# Motor_Controllers.net
KiCad netlist of a schematic drawn in Altium Designer
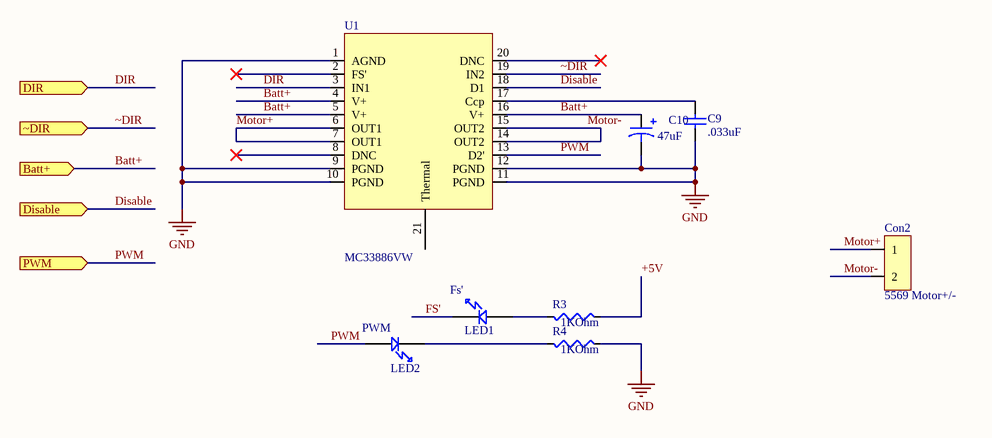
[diagram p0: Motor Controllers.SchDoc]

(export (version "E")
  (design (tool "Eeschema 10.0.6"))
  (components
    (comp (ref "C9")
      (value ".033uF")
      (footprint "PassiveComponents:0805 (2012) Capacitor")
      (description "Capacitor")
      (libsource (lib "PassiveComponents") (part "Capacitor (non-polarized)"))
    )
    (comp (ref "C10")
      (value "47uF")
      (footprint "PassiveComponents:Radial_6.3mmDia_SM_D")
      (description "Capacitor (polarized)")
      (libsource (lib "PassiveComponents") (part "Capacitor (polarized)"))
    )
    (comp (ref "Con2")
      (value "5569 Motor+/-")
      (footprint "Molex:5569 Mini-Fit Jr 2-Pos Right Angle w/ PCB Mounting Flange")
      (libsource (lib "Molex") (part "5569 Mini-Fit Jr 2-Pos Right Angle"))
    )
    (comp (ref "LED1")
      (value "Fs'")
      (footprint "LEDs:LED 0805")
      (description "Standard LED")
      (libsource (lib "PassiveComponents") (part "LED"))
    )
    (comp (ref "LED2")
      (value "PWM")
      (footprint "LEDs:LED 0805")
      (description "Standard LED")
      (libsource (lib "PassiveComponents") (part "LED"))
    )
    (comp (ref "R3")
      (value "1KOhm")
      (footprint "PassiveComponents:R 0805 (2012) RESISTOR")
      (description "Resistor")
      (libsource (lib "PassiveComponents") (part "Resistor"))
    )
    (comp (ref "R4")
      (value "1KOhm")
      (footprint "PassiveComponents:R 0805 (2012) RESISTOR")
      (description "Resistor")
      (libsource (lib "PassiveComponents") (part "Resistor"))
    )
    (comp (ref "U1")
      (value "MC33886VW")
      (footprint "SOP127P1420X340_HS-20N")
      (description "Motor Controller")
      (libsource (lib "MC33886VW") (part "MC33886VW"))
    )
  )
  (nets
    (net (code "1") (name "/+5V") (class "Default")
      (node (ref "R3") (pin "2") (pinfunction "2_2") (pintype "passive"))
    )
    (net (code "2") (name "/Batt+") (class "Default")
      (node (ref "C10") (pin "P") (pinfunction "1_P") (pintype "passive"))
      (node (ref "U1") (pin "16") (pinfunction "V+_16") (pintype "passive"))
      (node (ref "U1") (pin "4") (pinfunction "V+_4") (pintype "passive"))
      (node (ref "U1") (pin "5") (pinfunction "V+_5") (pintype "passive"))
    )
    (net (code "3") (name "/DIR") (class "Default")
      (node (ref "U1") (pin "3") (pinfunction "IN1_3") (pintype "passive"))
    )
    (net (code "4") (name "/Disable") (class "Default")
      (node (ref "U1") (pin "18") (pinfunction "D1_18") (pintype "passive"))
    )
    (net (code "5") (name "/FS'") (class "Default")
      (node (ref "LED1") (pin "1") (pinfunction "1_1") (pintype "passive"))
    )
    (net (code "6") (name "/Motor+") (class "Default")
      (node (ref "Con2") (pin "1") (pinfunction "1_1") (pintype "passive"))
      (node (ref "U1") (pin "6") (pinfunction "OUT1_6") (pintype "passive"))
      (node (ref "U1") (pin "7") (pinfunction "OUT1_7") (pintype "passive"))
    )
    (net (code "7") (name "/Motor-") (class "Default")
      (node (ref "Con2") (pin "2") (pinfunction "2_2") (pintype "passive"))
      (node (ref "U1") (pin "14") (pinfunction "OUT2_14") (pintype "passive"))
      (node (ref "U1") (pin "15") (pinfunction "OUT2_15") (pintype "passive"))
    )
    (net (code "8") (name "/PWM") (class "Default")
      (node (ref "LED2") (pin "2") (pinfunction "2_2") (pintype "passive"))
      (node (ref "U1") (pin "13") (pinfunction "D2'_13") (pintype "passive"))
    )
    (net (code "9") (name "/~DIR") (class "Default")
      (node (ref "U1") (pin "19") (pinfunction "IN2_19") (pintype "passive"))
    )
    (net (code "10") (name "GND") (class "Default")
      (node (ref "C10") (pin "N") (pinfunction "2_N") (pintype "passive"))
      (node (ref "C9") (pin "1") (pinfunction "1_1") (pintype "passive"))
      (node (ref "R4") (pin "2") (pinfunction "2_2") (pintype "passive"))
      (node (ref "U1") (pin "1") (pinfunction "AGND_1") (pintype "passive"))
      (node (ref "U1") (pin "10") (pinfunction "PGND_10") (pintype "passive"))
      (node (ref "U1") (pin "11") (pinfunction "PGND_11") (pintype "passive"))
      (node (ref "U1") (pin "12") (pinfunction "PGND_12") (pintype "passive"))
      (node (ref "U1") (pin "9") (pinfunction "PGND_9") (pintype "passive"))
    )
    (net (code "11") (name "Net-(LED1-Pad2)") (class "Default")
      (node (ref "LED1") (pin "2") (pinfunction "2_2") (pintype "passive"))
      (node (ref "R3") (pin "1") (pinfunction "1_1") (pintype "passive"))
    )
    (net (code "12") (name "Net-(LED2-Pad1)") (class "Default")
      (node (ref "LED2") (pin "1") (pinfunction "1_1") (pintype "passive"))
      (node (ref "R4") (pin "1") (pinfunction "1_1") (pintype "passive"))
    )
    (net (code "13") (name "Net-(U1-Ccp)") (class "Default")
      (node (ref "C9") (pin "2") (pinfunction "2_2") (pintype "passive"))
      (node (ref "U1") (pin "17") (pinfunction "Ccp_17") (pintype "passive"))
    )
    (net (code "14") (name "unconnected-(U1-DNC-Pad8)") (class "Default")
      (node (ref "U1") (pin "8") (pinfunction "DNC_8") (pintype "passive+no_connect"))
    )
    (net (code "15") (name "unconnected-(U1-DNC-Pad20)") (class "Default")
      (node (ref "U1") (pin "20") (pinfunction "DNC_20") (pintype "passive+no_connect"))
    )
    (net (code "16") (name "unconnected-(U1-FS'-Pad2)") (class "Default")
      (node (ref "U1") (pin "2") (pinfunction "FS'_2") (pintype "passive+no_connect"))
    )
    (net (code "17") (name "unconnected-(U1-Thermal-Pad21)") (class "Default")
      (node (ref "U1") (pin "21") (pinfunction "Thermal_21") (pintype "passive"))
    )
  )
)
